# sensor_board.net
KiCad netlist of a schematic drawn in EAGLE
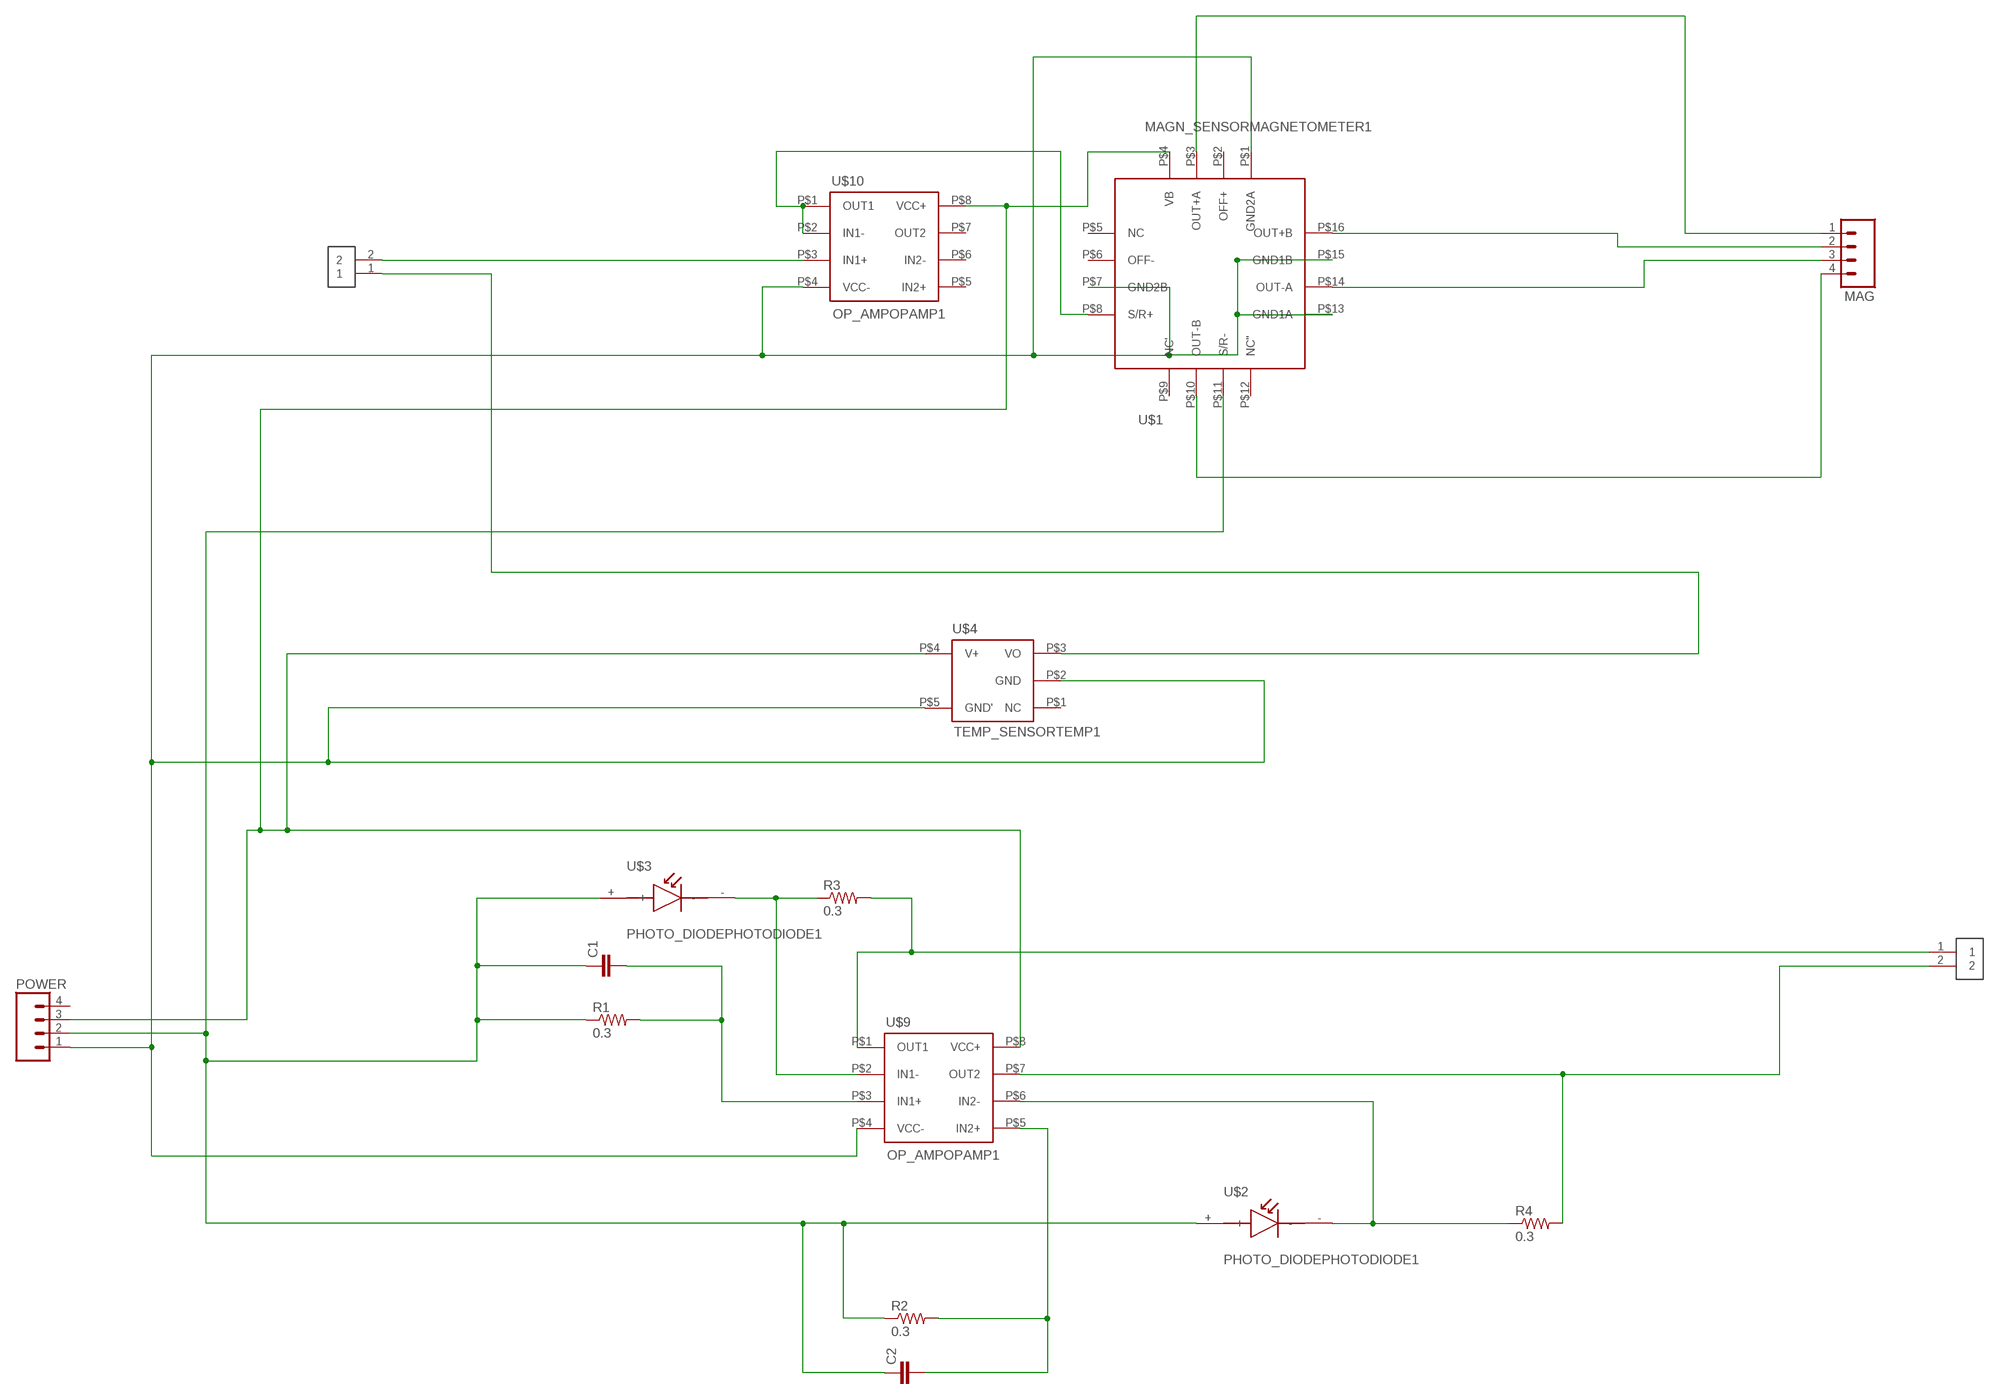
[diagram p0: schematic, sheet 1]

(export (version "E")
  (design (tool "Eeschema 10.0.6"))
  (components
    (comp (ref "C1")
      (value "CAP0402-CAP")
      (footprint "eagle-import:0402-CAP")
      (libsource (lib "eagle-import") (part "CAP0402-CAP"))
    )
    (comp (ref "C2")
      (value "CAP0402-CAP")
      (footprint "eagle-import:0402-CAP")
      (libsource (lib "eagle-import") (part "CAP0402-CAP"))
    )
    (comp (ref "MAG")
      (value "1X04_HEADER\"")
      (footprint "eagle-import:1X04_HEADER")
      (libsource (lib "eagle-import") (part "1X04_HEADER{dblquote}"))
    )
    (comp (ref "MAGSR_TEMP")
      (value "1X02_HEADER")
      (footprint "eagle-import:1X02_HEADER")
      (libsource (lib "eagle-import") (part "1X02_HEADER"))
    )
    (comp (ref "PHOTODIODE_OUT")
      (value "1X02_HEADER")
      (footprint "eagle-import:1X02_HEADER")
      (libsource (lib "eagle-import") (part "1X02_HEADER"))
    )
    (comp (ref "POWER")
      (value "1X04_HEADER\"")
      (footprint "eagle-import:1X04_HEADER")
      (libsource (lib "eagle-import") (part "1X04_HEADER{dblquote}"))
    )
    (comp (ref "R1")
      (value "0.3")
      (footprint "eagle-import:0805")
      (libsource (lib "eagle-import") (part "0.3OHM-1/8W-1%(0805)"))
    )
    (comp (ref "R2")
      (value "0.3")
      (footprint "eagle-import:0805")
      (libsource (lib "eagle-import") (part "0.3OHM-1/8W-1%(0805)"))
    )
    (comp (ref "R3")
      (value "0.3")
      (footprint "eagle-import:0805")
      (libsource (lib "eagle-import") (part "0.3OHM-1/8W-1%(0805)"))
    )
    (comp (ref "R4")
      (value "0.3")
      (footprint "eagle-import:0805")
      (libsource (lib "eagle-import") (part "0.3OHM-1/8W-1%(0805)"))
    )
    (comp (ref "U$1")
      (value "MAGN_SENSORMAGNETOMETER1")
      (footprint "eagle-import:MAGNETOMETER")
      (libsource (lib "eagle-import") (part "MAGN_SENSORMAGNETOMETER1"))
    )
    (comp (ref "U$2")
      (value "PHOTO_DIODEPHOTODIODE1")
      (footprint "eagle-import:PHOTODIODE")
      (libsource (lib "eagle-import") (part "PHOTO_DIODEPHOTODIODE1"))
    )
    (comp (ref "U$3")
      (value "PHOTO_DIODEPHOTODIODE1")
      (footprint "eagle-import:PHOTODIODE")
      (libsource (lib "eagle-import") (part "PHOTO_DIODEPHOTODIODE1"))
    )
    (comp (ref "U$4")
      (value "TEMP_SENSORTEMP1")
      (footprint "eagle-import:TEMP")
      (libsource (lib "eagle-import") (part "TEMP_SENSORTEMP1"))
    )
    (comp (ref "U$9")
      (value "OP_AMPOPAMP1")
      (footprint "eagle-import:OPAMP")
      (libsource (lib "eagle-import") (part "OP_AMPOPAMP1"))
    )
    (comp (ref "U$10")
      (value "OP_AMPOPAMP1")
      (footprint "eagle-import:OPAMP")
      (libsource (lib "eagle-import") (part "OP_AMPOPAMP1"))
    )
  )
  (nets
    (net (code "1") (name "Net-(U$1-GND1A)") (class "Default")
      (node (ref "POWER") (pin "1") (pinfunction "1_1") (pintype "passive"))
      (node (ref "U$1") (pin "P$1") (pinfunction "GND2A_P$1") (pintype "bidirectional"))
      (node (ref "U$1") (pin "P$13") (pinfunction "GND1A_P$13") (pintype "bidirectional"))
      (node (ref "U$1") (pin "P$15") (pinfunction "GND1B_P$15") (pintype "bidirectional"))
      (node (ref "U$1") (pin "P$7") (pinfunction "GND2B_P$7") (pintype "bidirectional"))
      (node (ref "U$10") (pin "P$4") (pinfunction "VCC-_P$4") (pintype "bidirectional"))
      (node (ref "U$4") (pin "P$2") (pinfunction "GND_P$2") (pintype "bidirectional"))
      (node (ref "U$4") (pin "P$5") (pinfunction "GND'_P$5") (pintype "bidirectional"))
      (node (ref "U$9") (pin "P$4") (pinfunction "VCC-_P$4") (pintype "bidirectional"))
    )
    (net (code "2") (name "Net-(U$1-OUT+A)") (class "Default")
      (node (ref "MAG") (pin "1") (pinfunction "1_1") (pintype "passive"))
      (node (ref "U$1") (pin "P$3") (pinfunction "OUT+A_P$3") (pintype "bidirectional"))
    )
    (net (code "3") (name "Net-(U$1-OUT+B)") (class "Default")
      (node (ref "MAG") (pin "2") (pinfunction "2_2") (pintype "passive"))
      (node (ref "U$1") (pin "P$16") (pinfunction "OUT+B_P$16") (pintype "bidirectional"))
    )
    (net (code "4") (name "Net-(U$1-OUT-A)") (class "Default")
      (node (ref "MAG") (pin "3") (pinfunction "3_3") (pintype "passive"))
      (node (ref "U$1") (pin "P$14") (pinfunction "OUT-A_P$14") (pintype "bidirectional"))
    )
    (net (code "5") (name "Net-(U$1-OUT-B)") (class "Default")
      (node (ref "MAG") (pin "4") (pinfunction "4_4") (pintype "passive"))
      (node (ref "U$1") (pin "P$10") (pinfunction "OUT-B_P$10") (pintype "bidirectional"))
    )
    (net (code "6") (name "Net-(U$1-S{slash}R+)") (class "Default")
      (node (ref "U$1") (pin "P$8") (pinfunction "S/R+_P$8") (pintype "bidirectional"))
      (node (ref "U$10") (pin "P$1") (pinfunction "OUT1_P$1") (pintype "bidirectional"))
      (node (ref "U$10") (pin "P$2") (pinfunction "IN1-_P$2") (pintype "bidirectional"))
    )
    (net (code "7") (name "Net-(U$1-S{slash}R-)") (class "Default")
      (node (ref "C1") (pin "1") (pinfunction "1_1") (pintype "passive"))
      (node (ref "C2") (pin "1") (pinfunction "1_1") (pintype "passive"))
      (node (ref "POWER") (pin "2") (pinfunction "2_2") (pintype "passive"))
      (node (ref "R1") (pin "1") (pinfunction "1_1") (pintype "passive"))
      (node (ref "R2") (pin "1") (pinfunction "1_1") (pintype "passive"))
      (node (ref "U$1") (pin "P$11") (pinfunction "S/R-_P$11") (pintype "bidirectional"))
      (node (ref "U$2") (pin "+") (pinfunction "+_+") (pintype "bidirectional"))
      (node (ref "U$3") (pin "+") (pinfunction "+_+") (pintype "bidirectional"))
    )
    (net (code "8") (name "Net-(U$1-VB)") (class "Default")
      (node (ref "POWER") (pin "3") (pinfunction "3_3") (pintype "passive"))
      (node (ref "U$1") (pin "P$4") (pinfunction "VB_P$4") (pintype "bidirectional"))
      (node (ref "U$10") (pin "P$8") (pinfunction "VCC+_P$8") (pintype "bidirectional"))
      (node (ref "U$4") (pin "P$4") (pinfunction "V+_P$4") (pintype "bidirectional"))
      (node (ref "U$9") (pin "P$8") (pinfunction "VCC+_P$8") (pintype "bidirectional"))
    )
    (net (code "9") (name "Net-(U$4-VO)") (class "Default")
      (node (ref "MAGSR_TEMP") (pin "1") (pinfunction "1_1") (pintype "bidirectional"))
      (node (ref "U$4") (pin "P$3") (pinfunction "VO_P$3") (pintype "bidirectional"))
    )
    (net (code "10") (name "Net-(U$9-IN1+)") (class "Default")
      (node (ref "C1") (pin "2") (pinfunction "2_2") (pintype "passive"))
      (node (ref "R1") (pin "2") (pinfunction "2_2") (pintype "passive"))
      (node (ref "U$9") (pin "P$3") (pinfunction "IN1+_P$3") (pintype "bidirectional"))
    )
    (net (code "11") (name "Net-(U$9-IN1-)") (class "Default")
      (node (ref "R3") (pin "1") (pinfunction "1_1") (pintype "passive"))
      (node (ref "U$3") (pin "-") (pinfunction "-_-") (pintype "bidirectional"))
      (node (ref "U$9") (pin "P$2") (pinfunction "IN1-_P$2") (pintype "bidirectional"))
    )
    (net (code "12") (name "Net-(U$9-IN2+)") (class "Default")
      (node (ref "C2") (pin "2") (pinfunction "2_2") (pintype "passive"))
      (node (ref "R2") (pin "2") (pinfunction "2_2") (pintype "passive"))
      (node (ref "U$9") (pin "P$5") (pinfunction "IN2+_P$5") (pintype "bidirectional"))
    )
    (net (code "13") (name "Net-(U$9-IN2-)") (class "Default")
      (node (ref "R4") (pin "1") (pinfunction "1_1") (pintype "passive"))
      (node (ref "U$2") (pin "-") (pinfunction "-_-") (pintype "bidirectional"))
      (node (ref "U$9") (pin "P$6") (pinfunction "IN2-_P$6") (pintype "bidirectional"))
    )
    (net (code "14") (name "Net-(U$9-OUT1)") (class "Default")
      (node (ref "PHOTODIODE_OUT") (pin "1") (pinfunction "1_1") (pintype "bidirectional"))
      (node (ref "R3") (pin "2") (pinfunction "2_2") (pintype "passive"))
      (node (ref "U$9") (pin "P$1") (pinfunction "OUT1_P$1") (pintype "bidirectional"))
    )
    (net (code "15") (name "Net-(U$9-OUT2)") (class "Default")
      (node (ref "PHOTODIODE_OUT") (pin "2") (pinfunction "2_2") (pintype "bidirectional"))
      (node (ref "R4") (pin "2") (pinfunction "2_2") (pintype "passive"))
      (node (ref "U$9") (pin "P$7") (pinfunction "OUT2_P$7") (pintype "bidirectional"))
    )
    (net (code "16") (name "Net-(U$10-IN1+)") (class "Default")
      (node (ref "MAGSR_TEMP") (pin "2") (pinfunction "2_2") (pintype "bidirectional"))
      (node (ref "U$10") (pin "P$3") (pinfunction "IN1+_P$3") (pintype "bidirectional"))
    )
    (net (code "17") (name "unconnected-(POWER-Pad4)") (class "Default")
      (node (ref "POWER") (pin "4") (pinfunction "4_4") (pintype "passive"))
    )
    (net (code "18") (name "unconnected-(U$1-NC''-PadP$12)") (class "Default")
      (node (ref "U$1") (pin "P$12") (pinfunction "NC''_P$12") (pintype "bidirectional"))
    )
    (net (code "19") (name "unconnected-(U$1-NC'-PadP$9)") (class "Default")
      (node (ref "U$1") (pin "P$9") (pinfunction "NC'_P$9") (pintype "bidirectional"))
    )
    (net (code "20") (name "unconnected-(U$1-NC-PadP$5)") (class "Default")
      (node (ref "U$1") (pin "P$5") (pinfunction "NC_P$5") (pintype "bidirectional"))
    )
    (net (code "21") (name "unconnected-(U$1-OFF+-PadP$2)") (class "Default")
      (node (ref "U$1") (pin "P$2") (pinfunction "OFF+_P$2") (pintype "bidirectional"))
    )
    (net (code "22") (name "unconnected-(U$1-OFF--PadP$6)") (class "Default")
      (node (ref "U$1") (pin "P$6") (pinfunction "OFF-_P$6") (pintype "bidirectional"))
    )
    (net (code "23") (name "unconnected-(U$4-NC-PadP$1)") (class "Default")
      (node (ref "U$4") (pin "P$1") (pinfunction "NC_P$1") (pintype "bidirectional"))
    )
    (net (code "24") (name "unconnected-(U$10-IN2+-PadP$5)") (class "Default")
      (node (ref "U$10") (pin "P$5") (pinfunction "IN2+_P$5") (pintype "bidirectional"))
    )
    (net (code "25") (name "unconnected-(U$10-IN2--PadP$6)") (class "Default")
      (node (ref "U$10") (pin "P$6") (pinfunction "IN2-_P$6") (pintype "bidirectional"))
    )
    (net (code "26") (name "unconnected-(U$10-OUT2-PadP$7)") (class "Default")
      (node (ref "U$10") (pin "P$7") (pinfunction "OUT2_P$7") (pintype "bidirectional"))
    )
  )
)
